# 1-.net
KiCad netlist of a schematic drawn in Altium Designer
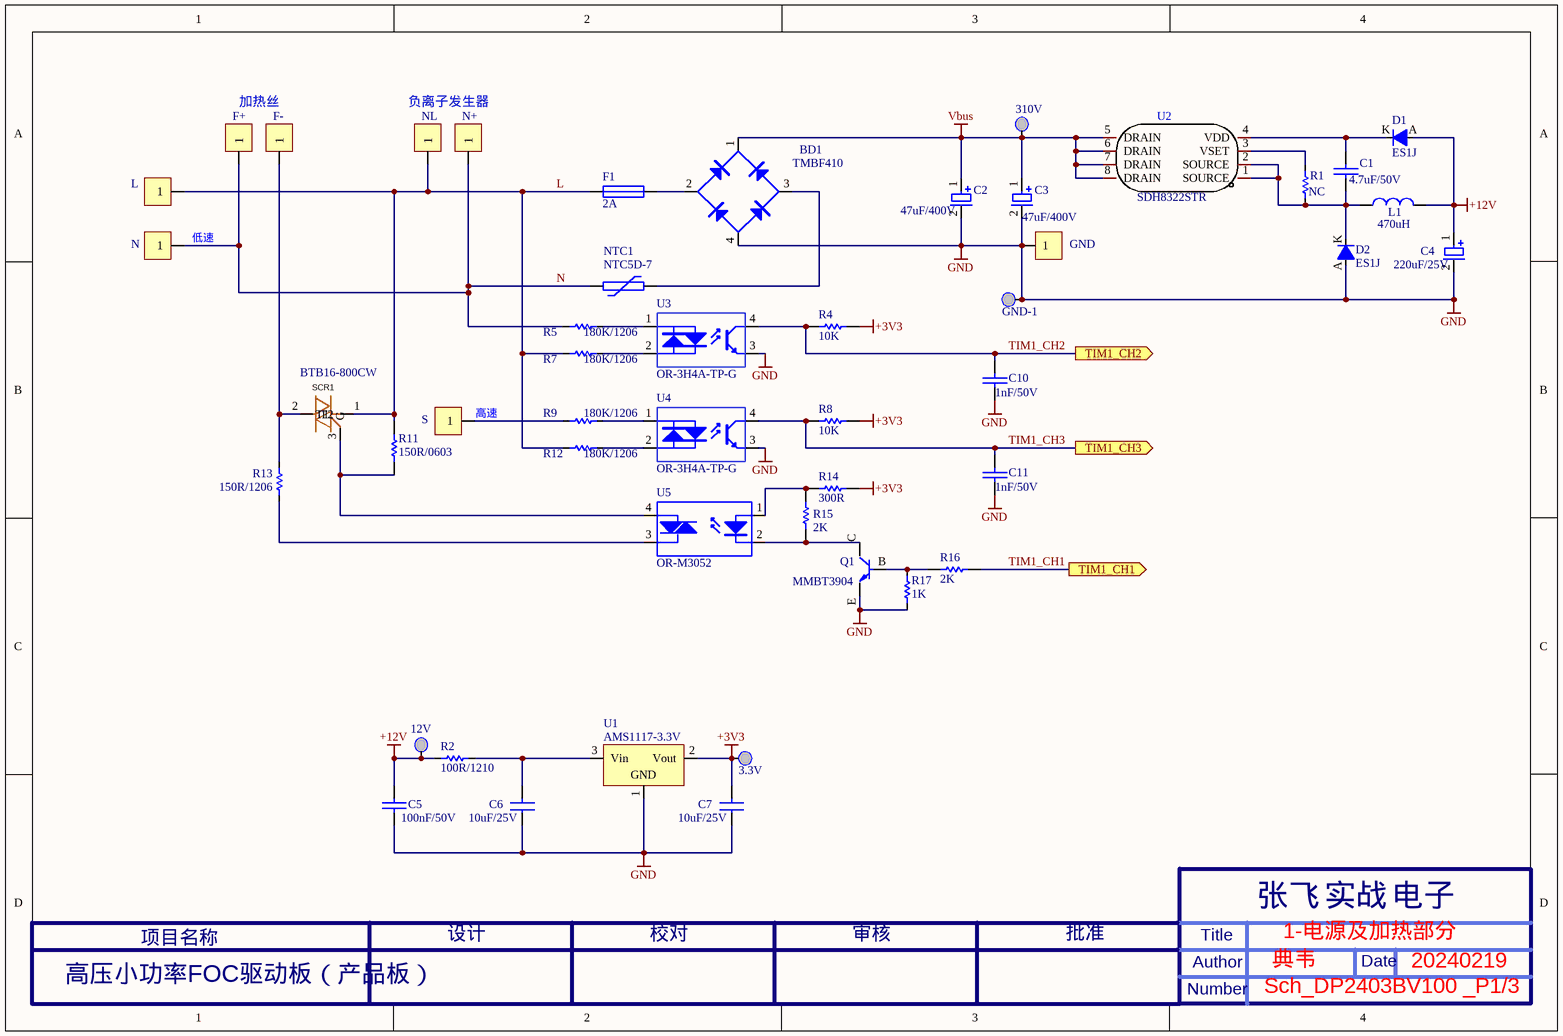
[diagram p0: 1-电源及加热部分.SchDoc]

(export (version "E")
  (design (tool "Eeschema 10.0.6"))
  (components
    (comp (ref "3.3V")
      (value "test point")
      (footprint "Test_Port")
      (libsource (lib "RUKING-Passive Component Schematic library V01") (part "test point"))
    )
    (comp (ref "12V") (value "test point") (footprint "Test_Port") (libsource (lib "") (part "test point_1")))
    (comp (ref "310V")
      (value "test point")
      (footprint "Test_Port")
      (libsource (lib "") (part "test point_1"))
    )
    (comp (ref "BD1")
      (value "TMBF410")
      (footprint "DBF")
      (description "贴片整流桥")
      (libsource (lib "ZF-V1.00(2022-6-13)") (part "BRIDGE1"))
    )
    (comp (ref "C1")
      (value "4.7uF/50V")
      (footprint "C0805")
      (description "贴片电容")
      (libsource (lib "*") (part "CAP"))
    )
    (comp (ref "C2")
      (value "47uF/400V")
      (footprint "D13/L21-5")
      (description "EWH2GM680L300T,D16*L30")
      (libsource (lib "ZF-V1.00(2022-6-13)") (part "CAP_EC"))
    )
    (comp (ref "C3")
      (value "47uF/400V")
      (footprint "D13/L21-5")
      (description "EWH2GM680L300T,D16*L30")
      (libsource (lib "ZF-V1.00(2022-6-13)") (part "CAP_EC"))
    )
    (comp (ref "C4")
      (value "220uF/25V")
      (footprint "RB3.5/8.2")
      (description "电解电容")
      (libsource (lib "ZF-V1.00(2022-6-13)") (part "CAP_EC"))
    )
    (comp (ref "C5")
      (value "100nF/50V")
      (footprint "C0603")
      (description "贴片电容")
      (libsource (lib "*") (part "CAP"))
    )
    (comp (ref "C6")
      (value "10uF/25V")
      (footprint "C0805")
      (description "贴片电容")
      (fields
        (field (name "VOLTAGE") "<Voltage>")
        (field (name "MANUFACTURER") "TDK")
        (field (name "CREATED BY") "JJJ")
      )
      (libsource (lib "*") (part "CAP NP_0"))
    )
    (comp (ref "C7")
      (value "10uF/25V")
      (footprint "C0805")
      (description "贴片电容")
      (fields
        (field (name "VOLTAGE") "<Voltage>")
        (field (name "MANUFACTURER") "TDK")
        (field (name "CREATED BY") "JJJ")
      )
      (libsource (lib "*") (part "CAP NP_0"))
    )
    (comp (ref "C10")
      (value "1nF/50V")
      (footprint "C0603")
      (description "贴片电容")
      (libsource (lib "*") (part "CAP"))
    )
    (comp (ref "C11")
      (value "1nF/50V")
      (footprint "C0603")
      (description "贴片电容")
      (libsource (lib "*") (part "CAP"))
    )
    (comp (ref "D1")
      (value "ES1J")
      (footprint "DO-214AC(SMA)")
      (description "二极管")
      (libsource (lib "ZF-V1.00(2022-6-13)") (part "DIO"))
    )
    (comp (ref "D2")
      (value "ES1J")
      (footprint "DO-214AC(SMA)")
      (description "二极管")
      (libsource (lib "ZF-V1.00(2022-6-13)") (part "DIO"))
    )
    (comp (ref "F+")
      (value "LT")
      (footprint "IGBT-PIN")
      (description "1Pin")
      (libsource (lib "") (part "Pin1_1"))
    )
    (comp (ref "F-")
      (value "T1")
      (footprint "IGBT-PIN")
      (description "1Pin")
      (libsource (lib "") (part "Pin1_1"))
    )
    (comp (ref "F1")
      (value "2A")
      (footprint "JFC2410-1200FS")
      (description "JFC2410-1200FS")
      (libsource (lib "ZF-V1.00(2022-6-13)") (part "FUSE1"))
    )
    (comp (ref "GND")
      (value "GND")
      (footprint "IGBT-PIN")
      (description "1Pin")
      (libsource (lib "") (part "Pin1_2"))
    )
    (comp (ref "GND-1")
      (value "test point")
      (footprint "Test_Port")
      (libsource (lib "") (part "test point_2"))
    )
    (comp (ref "L")
      (value "L")
      (footprint "IGBT-PIN")
      (description "1Pin")
      (libsource (lib "ZF-V1.00(2022-6-13)") (part "Pin1"))
    )
    (comp (ref "L1")
      (value "470uH")
      (footprint "L4.4/7")
      (description "电感")
      (libsource (lib "ZF-V1.00(2022-6-13)") (part "INDUCTOR"))
    )
    (comp (ref "N")
      (value "SL")
      (footprint "IGBT-PIN")
      (description "1Pin")
      (libsource (lib "ZF-V1.00(2022-6-13)") (part "Pin1"))
    )
    (comp (ref "N+")
      (value "NA")
      (footprint "IGBT-PIN")
      (description "1Pin")
      (libsource (lib "") (part "Pin1_1"))
    )
    (comp (ref "NL")
      (value "LA")
      (footprint "IGBT-PIN")
      (description "1Pin")
      (libsource (lib "") (part "Pin1_1"))
    )
    (comp (ref "NTC1")
      (value "NTC5D-7")
      (footprint "NTC-5D9")
      (description "热敏电阻")
      (libsource (lib "ZF-V1.00(2022-6-13)") (part "RES-NTC"))
    )
    (comp (ref "Q1")
      (value "MMBT3904")
      (footprint "SOT-23-BCE")
      (description "三极管")
      (libsource (lib "ZF_SchLib_V0.15") (part "BJT-NPN"))
    )
    (comp (ref "R1")
      (value "NC")
      (footprint "R1206")
      (description "电阻")
      (fields
        (field (name "MANUFACTURER") "Generic Components")
        (field (name "PUBLISHER") "Altium Hobart Technology Centre")
      )
      (libsource (lib "ZF-V1.00(2022-6-13)") (part "Res"))
    )
    (comp (ref "R2")
      (value "100R/1210")
      (footprint "R1210")
      (description "电阻")
      (fields
        (field (name "MANUFACTURER") "Generic Components")
        (field (name "PUBLISHER") "Altium Hobart Technology Centre")
      )
      (libsource (lib "ZF-V1.00(2022-6-13)") (part "Res"))
    )
    (comp (ref "R4")
      (value "10K")
      (footprint "R0603")
      (description "电阻")
      (fields
        (field (name "MANUFACTURER") "Generic Components")
        (field (name "PUBLISHER") "Altium Hobart Technology Centre")
      )
      (libsource (lib "ZF_SchLib_V0.15") (part "Res"))
    )
    (comp (ref "R5")
      (value "180K/1206")
      (footprint "R1206")
      (description "电阻")
      (fields
        (field (name "MANUFACTURER") "Generic Components")
        (field (name "PUBLISHER") "Altium Hobart Technology Centre")
      )
      (libsource (lib "ZF-V1.00(2022-6-13)") (part "Res"))
    )
    (comp (ref "R7")
      (value "180K/1206")
      (footprint "R1206")
      (description "电阻")
      (fields
        (field (name "MANUFACTURER") "Generic Components")
        (field (name "PUBLISHER") "Altium Hobart Technology Centre")
      )
      (libsource (lib "ZF-V1.00(2022-6-13)") (part "Res"))
    )
    (comp (ref "R8")
      (value "10K")
      (footprint "R0603")
      (description "电阻")
      (fields
        (field (name "MANUFACTURER") "Generic Components")
        (field (name "PUBLISHER") "Altium Hobart Technology Centre")
      )
      (libsource (lib "ZF_SchLib_V0.15") (part "Res"))
    )
    (comp (ref "R9")
      (value "180K/1206")
      (footprint "R1206")
      (description "电阻")
      (fields
        (field (name "MANUFACTURER") "Generic Components")
        (field (name "PUBLISHER") "Altium Hobart Technology Centre")
      )
      (libsource (lib "ZF-V1.00(2022-6-13)") (part "Res"))
    )
    (comp (ref "R11")
      (value "150R/0603")
      (footprint "R0603")
      (description "电阻")
      (fields
        (field (name "MANUFACTURER") "Generic Components")
        (field (name "PUBLISHER") "Altium Hobart Technology Centre")
      )
      (libsource (lib "ZF_SchLib_V0.15") (part "Res"))
    )
    (comp (ref "R12")
      (value "180K/1206")
      (footprint "R1206")
      (description "电阻")
      (fields
        (field (name "MANUFACTURER") "Generic Components")
        (field (name "PUBLISHER") "Altium Hobart Technology Centre")
      )
      (libsource (lib "ZF-V1.00(2022-6-13)") (part "Res"))
    )
    (comp (ref "R13")
      (value "150R/1206")
      (footprint "R1206")
      (description "电阻")
      (fields
        (field (name "MANUFACTURER") "Generic Components")
        (field (name "PUBLISHER") "Altium Hobart Technology Centre")
      )
      (libsource (lib "ZF-V1.00(2022-6-13)") (part "Res"))
    )
    (comp (ref "R14")
      (value "300R")
      (footprint "R0603")
      (description "电阻")
      (fields
        (field (name "MANUFACTURER") "Generic Components")
        (field (name "PUBLISHER") "Altium Hobart Technology Centre")
      )
      (libsource (lib "ZF_SchLib_V0.15") (part "Res"))
    )
    (comp (ref "R15")
      (value "2K")
      (footprint "R0603")
      (description "电阻")
      (fields
        (field (name "MANUFACTURER") "Generic Components")
        (field (name "PUBLISHER") "Altium Hobart Technology Centre")
      )
      (libsource (lib "ZF_SchLib_V0.15") (part "Res"))
    )
    (comp (ref "R16")
      (value "2K")
      (footprint "R0603")
      (description "电阻")
      (fields
        (field (name "MANUFACTURER") "Generic Components")
        (field (name "PUBLISHER") "Altium Hobart Technology Centre")
      )
      (libsource (lib "ZF_SchLib_V0.15") (part "Res"))
    )
    (comp (ref "R17")
      (value "1K")
      (footprint "R0603")
      (description "电阻")
      (fields
        (field (name "MANUFACTURER") "Generic Components")
        (field (name "PUBLISHER") "Altium Hobart Technology Centre")
      )
      (libsource (lib "ZF-V1.00(2022-6-13)") (part "Res"))
    )
    (comp (ref "S")
      (value "SH")
      (footprint "IGBT-PIN")
      (description "1Pin")
      (libsource (lib "ZF-V1.00(2022-6-13)") (part "Pin1"))
    )
    (comp (ref "SCR1")
      (value "BTB16-800CW")
      (footprint "TO-263")
      (description "可控硅")
      (fields (field (name "MANUFACTURER") "FUXINSEMI(富芯森美)") (field (name "MANUFACTURER PART") "BT136D"))
      (libsource (lib "ZF_SchLib_V0.04") (part "SCR-BT136D"))
    )
    (comp (ref "U1")
      (value "AMS1117-3.3V")
      (footprint "SOT-223")
      (description "LDO")
      (fields (field (name "PUBLISHER") "*"))
      (libsource (lib "ZF-V1.00(2022-6-13)") (part "AMS1117-3.3V"))
    )
    (comp (ref "U2")
      (value "SDH8322STR")
      (footprint "SOIC-8 - duplicate")
      (fields (field (name "MANUFACTURER") "SILAN(士兰微)"))
      (libsource (lib "altium-import") (part "root_2_SDH8322STR_"))
    )
    (comp (ref "U3")
      (value "OR-3H4A-TP-G")
      (footprint "dip4s")
      (libsource (lib "POWER_Project") (part "LTV-354T"))
    )
    (comp (ref "U4")
      (value "OR-3H4A-TP-G")
      (footprint "dip4s")
      (libsource (lib "POWER_Project") (part "LTV-354T"))
    )
    (comp (ref "U5")
      (value "OR-M3052")
      (footprint "SO-4")
      (libsource (lib "ZF-V1.00(2022-6-13)") (part "ORM305x"))
    )
  )
  (nets
    (net (code "1") (name "+3V3") (class "Default")
      (node (ref "3.3V") (pin "1") (pinfunction "Test_1") (pintype "passive"))
      (node (ref "C7") (pin "2") (pinfunction "2_2") (pintype "passive"))
      (node (ref "R14") (pin "2") (pinfunction "2_2") (pintype "passive"))
      (node (ref "R4") (pin "2") (pinfunction "2_2") (pintype "passive"))
      (node (ref "R8") (pin "1") (pinfunction "1_1") (pintype "passive"))
      (node (ref "U1") (pin "2") (pinfunction "Vout_2") (pintype "passive"))
    )
    (net (code "2") (name "+12V") (class "Default")
      (node (ref "12V") (pin "1") (pinfunction "Test_1") (pintype "passive"))
      (node (ref "C4") (pin "1") (pinfunction "1_1") (pintype "passive"))
      (node (ref "C5") (pin "1") (pinfunction "1_1") (pintype "passive"))
      (node (ref "D1") (pin "A") (pinfunction "A_A") (pintype "passive"))
      (node (ref "L1") (pin "2") (pinfunction "2_2") (pintype "passive"))
      (node (ref "R2") (pin "2") (pinfunction "2_2") (pintype "passive"))
    )
    (net (code "3") (name "/L") (class "Default")
      (node (ref "F1") (pin "1") (pintype "passive"))
      (node (ref "L") (pin "1") (pinfunction "1_1") (pintype "passive"))
      (node (ref "NL") (pin "1") (pinfunction "1_1") (pintype "passive"))
      (node (ref "R11") (pin "2") (pinfunction "2_2") (pintype "passive"))
      (node (ref "R12") (pin "1") (pinfunction "1_1") (pintype "passive"))
      (node (ref "R7") (pin "1") (pinfunction "1_1") (pintype "passive"))
      (node (ref "SCR1") (pin "1") (pinfunction "T1_1") (pintype "passive"))
    )
    (net (code "4") (name "/N") (class "Default")
      (node (ref "F+") (pin "1") (pinfunction "1_1") (pintype "passive"))
      (node (ref "N") (pin "1") (pinfunction "1_1") (pintype "passive"))
      (node (ref "N+") (pin "1") (pinfunction "1_1") (pintype "passive"))
      (node (ref "NTC1") (pin "1") (pintype "passive"))
      (node (ref "R5") (pin "1") (pinfunction "1_1") (pintype "passive"))
    )
    (net (code "5") (name "/TIM1_CH1") (class "Default")
      (node (ref "R16") (pin "2") (pinfunction "2_2") (pintype "passive"))
    )
    (net (code "6") (name "/TIM1_CH2") (class "Default")
      (node (ref "C10") (pin "1") (pinfunction "1_1") (pintype "passive"))
      (node (ref "R4") (pin "1") (pinfunction "1_1") (pintype "passive"))
      (node (ref "U3") (pin "4") (pinfunction "C_4") (pintype "passive"))
    )
    (net (code "7") (name "/TIM1_CH3") (class "Default")
      (node (ref "C11") (pin "1") (pinfunction "1_1") (pintype "passive"))
      (node (ref "R8") (pin "2") (pinfunction "2_2") (pintype "passive"))
      (node (ref "U4") (pin "4") (pinfunction "C_4") (pintype "passive"))
    )
    (net (code "8") (name "GND") (class "Default")
      (node (ref "BD1") (pin "4") (pintype "passive"))
      (node (ref "C10") (pin "2") (pinfunction "2_2") (pintype "passive"))
      (node (ref "C11") (pin "2") (pinfunction "2_2") (pintype "passive"))
      (node (ref "C2") (pin "2") (pinfunction "2_2") (pintype "passive"))
      (node (ref "C3") (pin "2") (pinfunction "2_2") (pintype "passive"))
      (node (ref "C4") (pin "2") (pinfunction "2_2") (pintype "passive"))
      (node (ref "C5") (pin "2") (pinfunction "2_2") (pintype "passive"))
      (node (ref "C6") (pin "1") (pinfunction "1_1") (pintype "passive"))
      (node (ref "C7") (pin "1") (pinfunction "1_1") (pintype "passive"))
      (node (ref "D2") (pin "A") (pinfunction "A_A") (pintype "passive"))
      (node (ref "GND") (pin "1") (pinfunction "1_1") (pintype "passive"))
      (node (ref "GND-1") (pin "1") (pinfunction "Test_1") (pintype "passive"))
      (node (ref "Q1") (pin "E") (pinfunction "2_E") (pintype "passive"))
      (node (ref "R17") (pin "2") (pinfunction "2_2") (pintype "passive"))
      (node (ref "U1") (pin "1") (pinfunction "GND_1") (pintype "passive"))
      (node (ref "U3") (pin "3") (pinfunction "E_3") (pintype "passive"))
      (node (ref "U4") (pin "3") (pinfunction "E_3") (pintype "passive"))
    )
    (net (code "9") (name "Net-(BD1-Pad2)") (class "Default")
      (node (ref "BD1") (pin "2") (pintype "passive"))
      (node (ref "F1") (pin "2") (pintype "passive"))
    )
    (net (code "10") (name "Net-(BD1-Pad3)") (class "Default")
      (node (ref "BD1") (pin "3") (pintype "passive"))
      (node (ref "NTC1") (pin "2") (pintype "passive"))
    )
    (net (code "11") (name "Net-(C1-Pad2)") (class "Default")
      (node (ref "C1") (pin "2") (pinfunction "2_2") (pintype "passive"))
      (node (ref "D2") (pin "K") (pinfunction "K_K") (pintype "passive"))
      (node (ref "L1") (pin "1") (pinfunction "1_1") (pintype "passive"))
      (node (ref "R1") (pin "1") (pinfunction "1_1") (pintype "passive"))
      (node (ref "U2") (pin "1") (pinfunction "SOURCE_1") (pintype "passive"))
      (node (ref "U2") (pin "2") (pinfunction "SOURCE_2") (pintype "passive"))
    )
    (net (code "12") (name "Net-(Q1-1)") (class "Default")
      (node (ref "Q1") (pin "B") (pinfunction "1_B") (pintype "passive"))
      (node (ref "R16") (pin "1") (pinfunction "1_1") (pintype "passive"))
      (node (ref "R17") (pin "1") (pinfunction "1_1") (pintype "passive"))
    )
    (net (code "13") (name "Net-(Q1-3)") (class "Default")
      (node (ref "Q1") (pin "C") (pinfunction "3_C") (pintype "passive"))
      (node (ref "R15") (pin "1") (pinfunction "1_1") (pintype "passive"))
      (node (ref "U5") (pin "2") (pintype "passive"))
    )
    (net (code "14") (name "Net-(R9-Pad1)") (class "Default")
      (node (ref "R9") (pin "1") (pinfunction "1_1") (pintype "passive"))
      (node (ref "S") (pin "1") (pinfunction "1_1") (pintype "passive"))
    )
    (net (code "15") (name "Net-(R13-Pad2)") (class "Default")
      (node (ref "R13") (pin "2") (pinfunction "2_2") (pintype "passive"))
      (node (ref "U5") (pin "3") (pintype "passive"))
    )
    (net (code "16") (name "Net-(R14-Pad1)") (class "Default")
      (node (ref "R14") (pin "1") (pinfunction "1_1") (pintype "passive"))
      (node (ref "R15") (pin "2") (pinfunction "2_2") (pintype "passive"))
      (node (ref "U5") (pin "1") (pintype "passive"))
    )
    (net (code "17") (name "Net-(SCR1-G)") (class "Default")
      (node (ref "R11") (pin "1") (pinfunction "1_1") (pintype "passive"))
      (node (ref "SCR1") (pin "3") (pinfunction "G_3") (pintype "passive"))
      (node (ref "U5") (pin "4") (pintype "passive"))
    )
    (net (code "18") (name "Net-(SCR1-T2)") (class "Default")
      (node (ref "F-") (pin "1") (pinfunction "1_1") (pintype "passive"))
      (node (ref "R13") (pin "1") (pinfunction "1_1") (pintype "passive"))
      (node (ref "SCR1") (pin "2") (pinfunction "T2_2") (pintype "passive"))
    )
    (net (code "19") (name "Net-(U1-Vin)") (class "Default")
      (node (ref "C6") (pin "2") (pinfunction "2_2") (pintype "passive"))
      (node (ref "R2") (pin "1") (pinfunction "1_1") (pintype "passive"))
      (node (ref "U1") (pin "3") (pinfunction "Vin_3") (pintype "passive"))
    )
    (net (code "20") (name "Net-(U2-VDD)") (class "Default")
      (node (ref "C1") (pin "1") (pinfunction "1_1") (pintype "passive"))
      (node (ref "D1") (pin "K") (pinfunction "K_K") (pintype "passive"))
      (node (ref "U2") (pin "4") (pinfunction "VDD_4") (pintype "passive"))
    )
    (net (code "21") (name "Net-(U2-VSET)") (class "Default")
      (node (ref "R1") (pin "2") (pinfunction "2_2") (pintype "passive"))
      (node (ref "U2") (pin "3") (pinfunction "VSET_3") (pintype "passive"))
    )
    (net (code "22") (name "Net-(U3-A)") (class "Default")
      (node (ref "R5") (pin "2") (pinfunction "2_2") (pintype "passive"))
      (node (ref "U3") (pin "1") (pinfunction "A_1") (pintype "passive"))
    )
    (net (code "23") (name "Net-(U3-K)") (class "Default")
      (node (ref "R7") (pin "2") (pinfunction "2_2") (pintype "passive"))
      (node (ref "U3") (pin "2") (pinfunction "K_2") (pintype "passive"))
    )
    (net (code "24") (name "Net-(U4-A)") (class "Default")
      (node (ref "R9") (pin "2") (pinfunction "2_2") (pintype "passive"))
      (node (ref "U4") (pin "1") (pinfunction "A_1") (pintype "passive"))
    )
    (net (code "25") (name "Net-(U4-K)") (class "Default")
      (node (ref "R12") (pin "2") (pinfunction "2_2") (pintype "passive"))
      (node (ref "U4") (pin "2") (pinfunction "K_2") (pintype "passive"))
    )
    (net (code "26") (name "Vbus") (class "Default")
      (node (ref "310V") (pin "1") (pinfunction "Test_1") (pintype "passive"))
      (node (ref "BD1") (pin "1") (pintype "passive"))
      (node (ref "C2") (pin "1") (pinfunction "1_1") (pintype "passive"))
      (node (ref "C3") (pin "1") (pinfunction "1_1") (pintype "passive"))
      (node (ref "U2") (pin "5") (pinfunction "DRAIN_5") (pintype "passive"))
      (node (ref "U2") (pin "6") (pinfunction "DRAIN_6") (pintype "passive"))
      (node (ref "U2") (pin "7") (pinfunction "DRAIN_7") (pintype "passive"))
      (node (ref "U2") (pin "8") (pinfunction "DRAIN_8") (pintype "passive"))
    )
  )
)
